# ProPrj_wildCat_2025-03-20.net
KiCad netlist of a schematic drawn in EasyEDA Pro
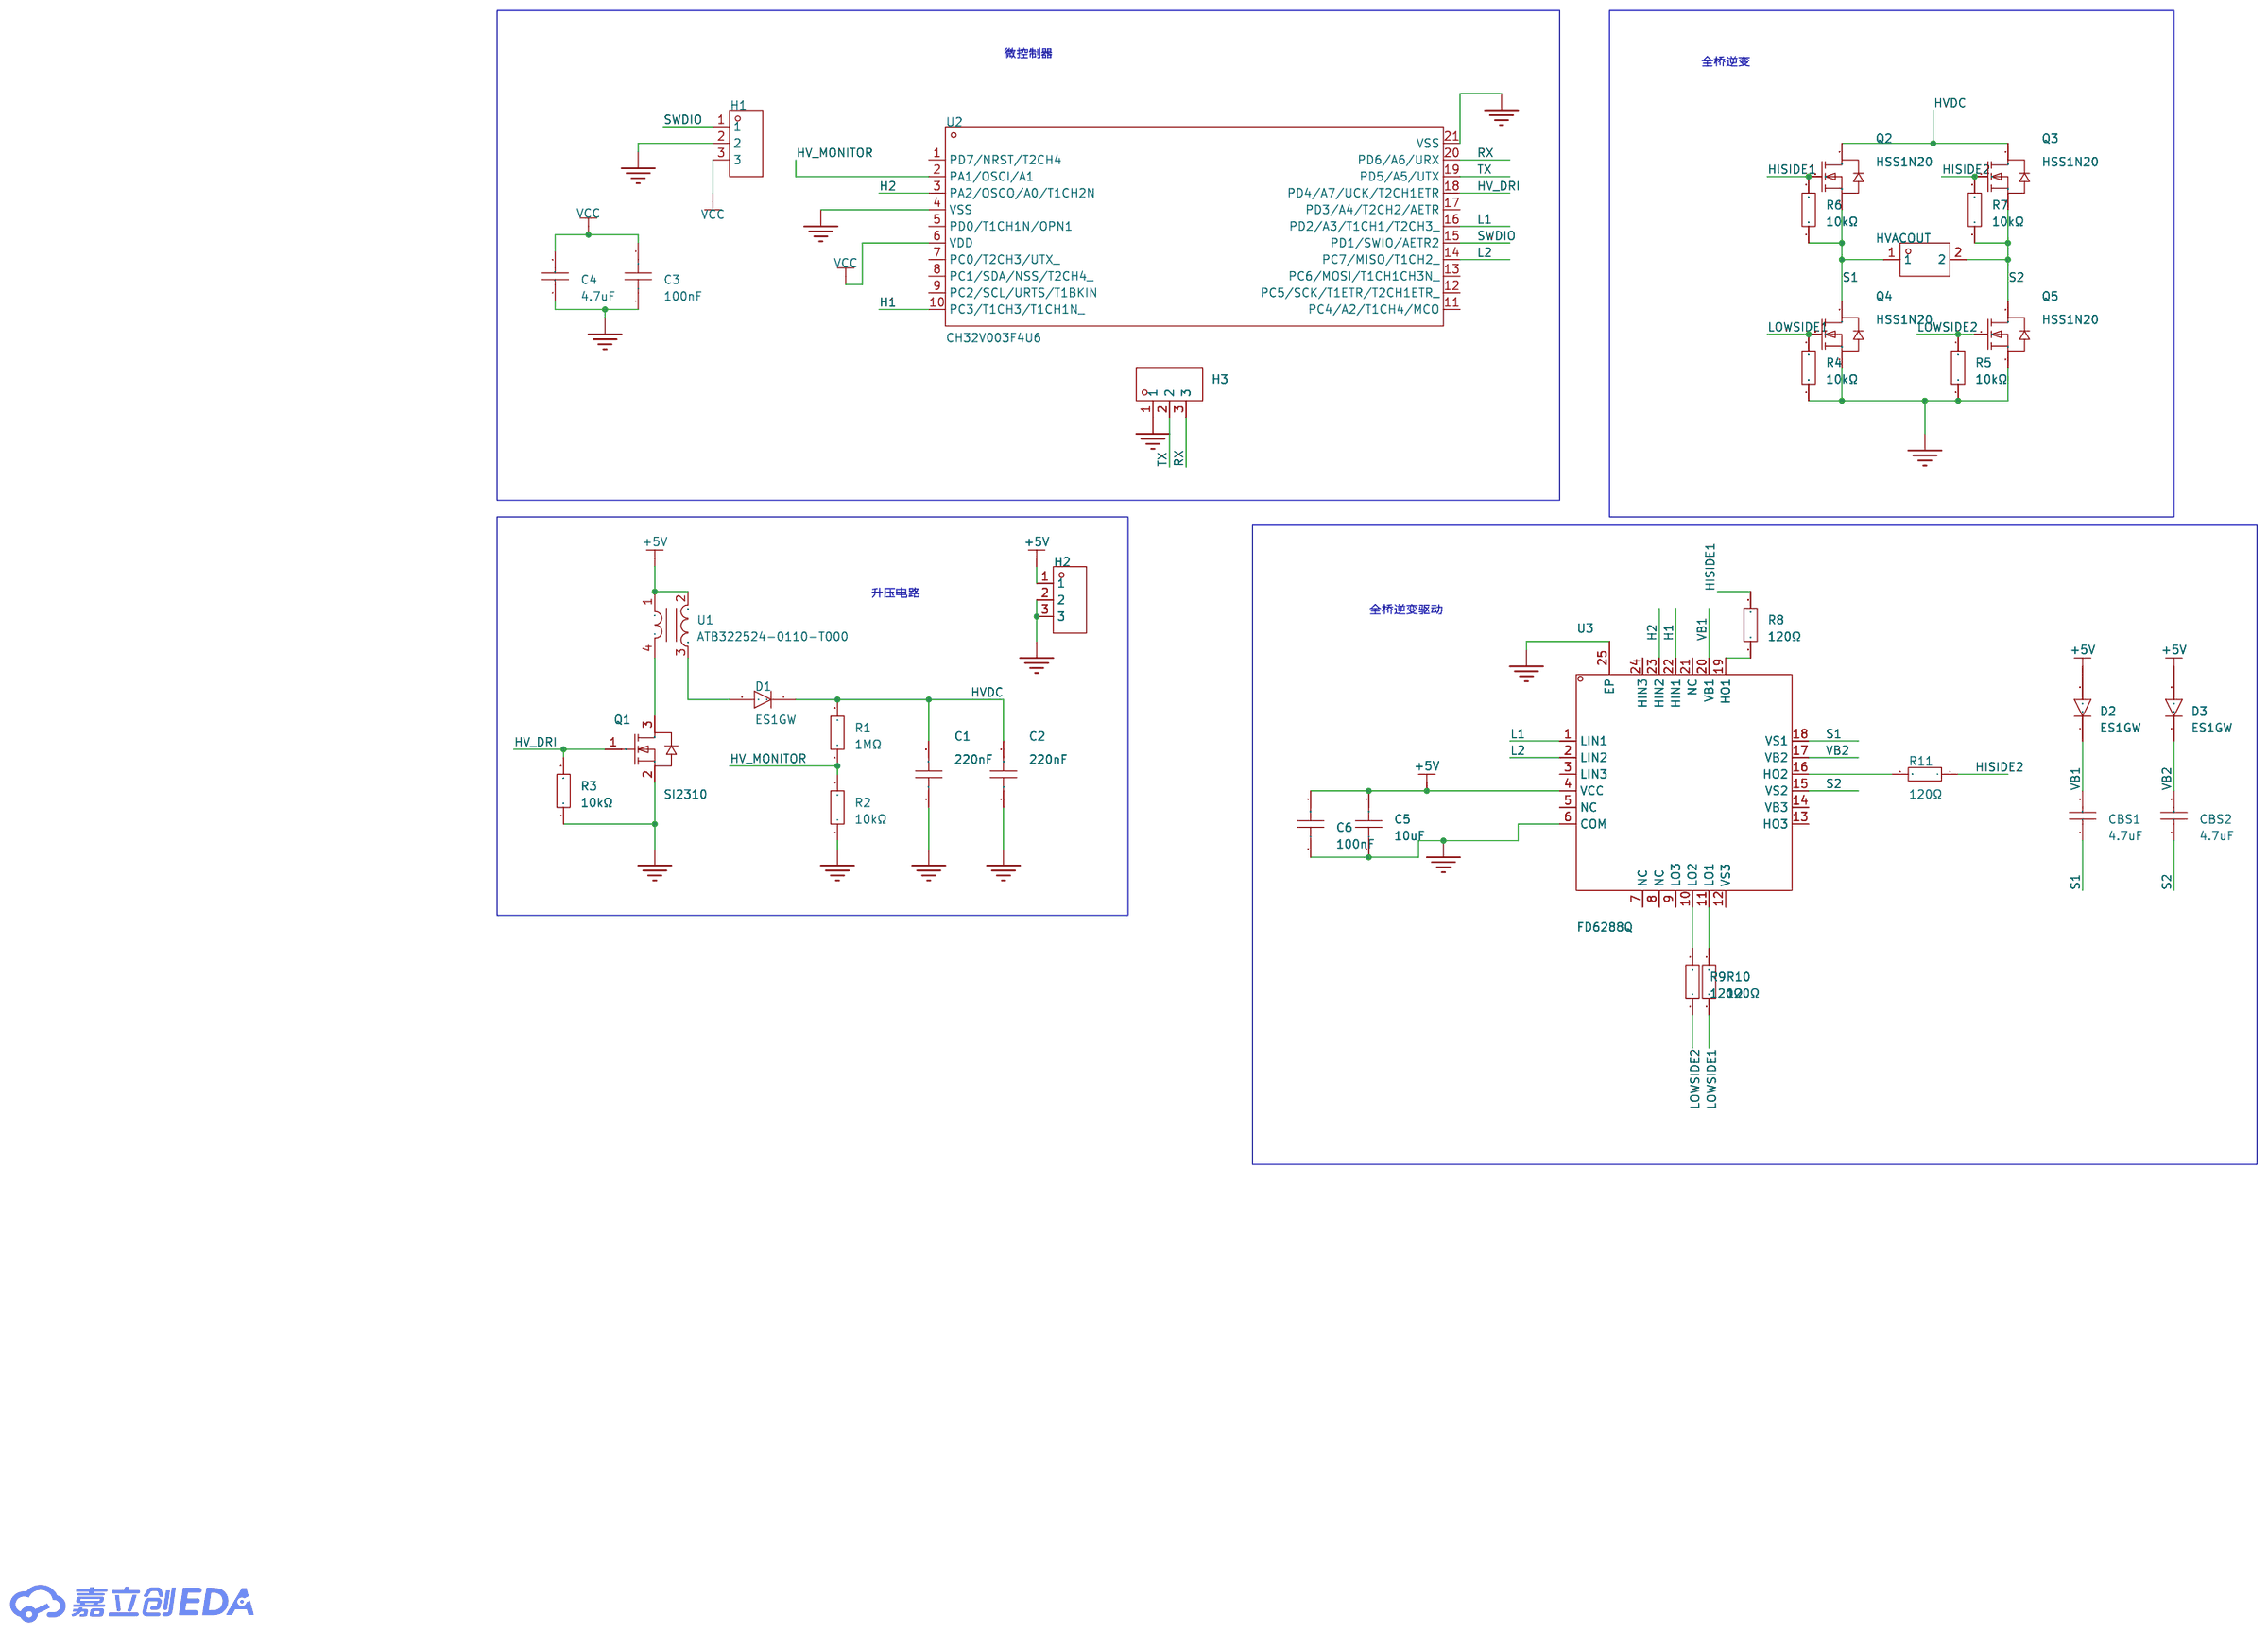
[diagram p0: schematic sheet]

(export (version "E")
  (design (tool "Eeschema 10.0.6"))
  (components
    (comp (ref "C1")
      (value "220nF")
      (footprint "easyedapro:C1210")
      (description "容值:220nF;精度:±10%;额定电压:250V;材质(温度系数):X7R;")
      (fields
        (field (name "Manufacturer Part") "CC1210KKX7RYBB224")
        (field (name "Manufacturer") "YAGEO(国巨)")
      )
      (libsource (lib "easyedapro") (part "CC1210KKX7RYBB224"))
    )
    (comp (ref "C2")
      (value "220nF")
      (footprint "easyedapro:C1210")
      (description "容值:220nF;精度:±10%;额定电压:250V;材质(温度系数):X7R;")
      (fields
        (field (name "Manufacturer Part") "CC1210KKX7RYBB224")
        (field (name "Manufacturer") "YAGEO(国巨)")
      )
      (libsource (lib "easyedapro") (part "CC1210KKX7RYBB224"))
    )
    (comp (ref "C3")
      (value "100nF")
      (footprint "easyedapro:C0603")
      (description "容值:100nF;精度:±10%;额定电压:50V;温度系数:X7R;")
      (fields
        (field (name "Manufacturer Part") "CGA0603X7R104K500JT")
        (field (name "Manufacturer") "HRE(芯声)")
      )
      (libsource (lib "easyedapro") (part "CGA0603X7R104K500JT"))
    )
    (comp (ref "C4")
      (value "4.7uF")
      (footprint "easyedapro:C0805")
      (description "容值:4.7uF;精度:±10%;额定电压:50V;材质(温度系数):X5R;")
      (fields
        (field (name "Manufacturer Part") "CL21A475KBQNNNE")
        (field (name "Manufacturer") "SAMSUNG(三星)")
      )
      (libsource (lib "easyedapro") (part "CL21A475KBQNNNE"))
    )
    (comp (ref "C5")
      (value "10uF")
      (footprint "easyedapro:C1206")
      (description "容值:10uF;精度:±10%;额定电压:50V;温度系数:X5R;")
      (fields
        (field (name "Manufacturer Part") "HGC1206R5106K500NSPJ")
        (field (name "Manufacturer") "Chinocera(华瓷)")
      )
      (libsource (lib "easyedapro") (part "HGC1206R5106K500NSPJ"))
    )
    (comp (ref "C6")
      (value "100nF")
      (footprint "easyedapro:C0603")
      (description "容值:100nF;精度:±10%;额定电压:50V;温度系数:X7R;")
      (fields
        (field (name "Manufacturer Part") "CGA0603X7R104K500JT")
        (field (name "Manufacturer") "HRE(芯声)")
      )
      (libsource (lib "easyedapro") (part "CGA0603X7R104K500JT"))
    )
    (comp (ref "CBS1")
      (value "4.7uF")
      (footprint "easyedapro:C0805")
      (description "容值:4.7uF;精度:±10%;额定电压:50V;材质(温度系数):X5R;")
      (fields
        (field (name "Manufacturer Part") "CL21A475KBQNNNE")
        (field (name "Manufacturer") "SAMSUNG(三星)")
      )
      (libsource (lib "easyedapro") (part "CL21A475KBQNNNE"))
    )
    (comp (ref "CBS2")
      (value "4.7uF")
      (footprint "easyedapro:C0805")
      (description "容值:4.7uF;精度:±10%;额定电压:50V;材质(温度系数):X5R;")
      (fields
        (field (name "Manufacturer Part") "CL21A475KBQNNNE")
        (field (name "Manufacturer") "SAMSUNG(三星)")
      )
      (libsource (lib "easyedapro") (part "CL21A475KBQNNNE"))
    )
    (comp (ref "D1")
      (value "ES1GW")
      (footprint "easyedapro:SOD-123FL_L2.7-W1.8-LS3.8-RD")
      (description "二极管配置:独立式;正向压降(Vf):1.25V@1A;直流反向耐压(Vr):400V;整流电流:1A;反向恢复时间(trr):35ns;")
      (fields (field (name "Manufacturer") "晶导微电子"))
      (libsource (lib "easyedapro") (part "ES1GW"))
    )
    (comp (ref "D2")
      (value "ES1GW")
      (footprint "easyedapro:SOD-123FL_L2.7-W1.8-LS3.8-RD")
      (description "二极管配置:独立式;正向压降(Vf):1.25V@1A;直流反向耐压(Vr):400V;整流电流:1A;反向恢复时间(trr):35ns;")
      (fields (field (name "Manufacturer") "晶导微电子"))
      (libsource (lib "easyedapro") (part "ES1GW"))
    )
    (comp (ref "D3")
      (value "ES1GW")
      (footprint "easyedapro:SOD-123FL_L2.7-W1.8-LS3.8-RD")
      (description "二极管配置:独立式;正向压降(Vf):1.25V@1A;直流反向耐压(Vr):400V;整流电流:1A;反向恢复时间(trr):35ns;")
      (fields (field (name "Manufacturer") "晶导微电子"))
      (libsource (lib "easyedapro") (part "ES1GW"))
    )
    (comp (ref "H1")
      (value "~")
      (footprint "easyedapro:HDR-TH_3P-P2.54-V-F")
      (libsource (lib "easyedapro") (part "PM254V-11-03-H85"))
    )
    (comp (ref "H2")
      (value "~")
      (footprint "easyedapro:HDR-TH_3P-P2.54-V-F")
      (libsource (lib "easyedapro") (part "PM254V-11-03-H85"))
    )
    (comp (ref "H3")
      (value "~")
      (footprint "easyedapro:HDR-TH_3P-P2.54-V-F")
      (libsource (lib "easyedapro") (part "PM254V-11-03-H85"))
    )
    (comp (ref "HVACOUT")
      (value "~")
      (footprint "easyedapro:HDR-TH_2P-P2.54-V-M-2")
      (libsource (lib "easyedapro") (part "HDR-M-2.54_2x1"))
    )
    (comp (ref "Q1")
      (value "SI2310")
      (footprint "easyedapro:SOT-23_L2.9-W1.3-P1.90-LS2.4-BR")
      (description "类型:-;漏源电压(Vdss):60V;连续漏极电流(Id):3A;导通电阻(RDS(on)):125mΩ@4.5V,3A;耗散功率(Pd):1.5W;阈值电压(Vgs(th)):500mV;")
      (fields (field (name "Manufacturer") "GOODWORK(固得沃克)"))
      (libsource (lib "easyedapro") (part "SI2310_C2938374"))
    )
    (comp (ref "Q2")
      (value "HSS1N20")
      (footprint "easyedapro:SOT-23-3_L2.9-W1.6-P1.90-LS2.8-BR")
      (fields (field (name "Manufacturer") "HUASHUO(华朔)"))
      (libsource (lib "easyedapro") (part "HSS1N20"))
    )
    (comp (ref "Q3")
      (value "HSS1N20")
      (footprint "easyedapro:SOT-23-3_L2.9-W1.6-P1.90-LS2.8-BR")
      (fields (field (name "Manufacturer") "HUASHUO(华朔)"))
      (libsource (lib "easyedapro") (part "HSS1N20"))
    )
    (comp (ref "Q4")
      (value "HSS1N20")
      (footprint "easyedapro:SOT-23-3_L2.9-W1.6-P1.90-LS2.8-BR")
      (fields (field (name "Manufacturer") "HUASHUO(华朔)"))
      (libsource (lib "easyedapro") (part "HSS1N20"))
    )
    (comp (ref "Q5")
      (value "HSS1N20")
      (footprint "easyedapro:SOT-23-3_L2.9-W1.6-P1.90-LS2.8-BR")
      (fields (field (name "Manufacturer") "HUASHUO(华朔)"))
      (libsource (lib "easyedapro") (part "HSS1N20"))
    )
    (comp (ref "R1")
      (value "1MΩ")
      (footprint "easyedapro:R0603")
      (description "电阻类型:厚膜电阻;阻值:1MΩ;精度:±1%;功率:100mW;最大工作电压:75V;温度系数:±100ppm/°C;")
      (fields
        (field (name "Manufacturer Part") "0603WAF1004T5E")
        (field (name "Manufacturer") "UNI-ROYAL(厚声)")
      )
      (libsource (lib "easyedapro") (part "0603WAF1004T5E"))
    )
    (comp (ref "R2")
      (value "10kΩ")
      (footprint "easyedapro:R0402")
      (description "电阻类型:厚膜电阻;阻值:10kΩ;精度:±1%;功率:62.5mW;最大工作电压:50V;温度系数:±100ppm/°C;")
      (fields
        (field (name "Manufacturer Part") "0603WAF1002T5E")
        (field (name "Manufacturer") "UNI-ROYAL(厚声)")
      )
      (libsource (lib "easyedapro") (part "0402WGF1002TCE"))
    )
    (comp (ref "R3")
      (value "10kΩ")
      (footprint "easyedapro:R0402")
      (description "电阻类型:厚膜电阻;阻值:10kΩ;精度:±1%;功率:62.5mW;最大工作电压:50V;温度系数:±100ppm/°C;")
      (fields
        (field (name "Manufacturer Part") "0603WAF1002T5E")
        (field (name "Manufacturer") "UNI-ROYAL(厚声)")
      )
      (libsource (lib "easyedapro") (part "0402WGF1002TCE"))
    )
    (comp (ref "R4")
      (value "10kΩ")
      (footprint "easyedapro:R0402")
      (description "电阻类型:厚膜电阻;阻值:10kΩ;精度:±1%;功率:62.5mW;最大工作电压:50V;温度系数:±100ppm/°C;")
      (fields
        (field (name "Manufacturer Part") "0603WAF1002T5E")
        (field (name "Manufacturer") "UNI-ROYAL(厚声)")
      )
      (libsource (lib "easyedapro") (part "0402WGF1002TCE"))
    )
    (comp (ref "R5")
      (value "10kΩ")
      (footprint "easyedapro:R0402")
      (description "电阻类型:厚膜电阻;阻值:10kΩ;精度:±1%;功率:62.5mW;最大工作电压:50V;温度系数:±100ppm/°C;")
      (fields
        (field (name "Manufacturer Part") "0603WAF1002T5E")
        (field (name "Manufacturer") "UNI-ROYAL(厚声)")
      )
      (libsource (lib "easyedapro") (part "0402WGF1002TCE"))
    )
    (comp (ref "R6")
      (value "10kΩ")
      (footprint "easyedapro:R0402")
      (description "电阻类型:厚膜电阻;阻值:10kΩ;精度:±1%;功率:62.5mW;最大工作电压:50V;温度系数:±100ppm/°C;")
      (fields
        (field (name "Manufacturer Part") "0603WAF1002T5E")
        (field (name "Manufacturer") "UNI-ROYAL(厚声)")
      )
      (libsource (lib "easyedapro") (part "0402WGF1002TCE"))
    )
    (comp (ref "R7")
      (value "10kΩ")
      (footprint "easyedapro:R0402")
      (description "电阻类型:厚膜电阻;阻值:10kΩ;精度:±1%;功率:62.5mW;最大工作电压:50V;温度系数:±100ppm/°C;")
      (fields
        (field (name "Manufacturer Part") "0603WAF1002T5E")
        (field (name "Manufacturer") "UNI-ROYAL(厚声)")
      )
      (libsource (lib "easyedapro") (part "0402WGF1002TCE"))
    )
    (comp (ref "R8")
      (value "120Ω")
      (footprint "easyedapro:R0603")
      (description "电阻类型:厚膜电阻;阻值:120Ω;精度:±1%;功率:100mW;最大工作电压:75V;温度系数:±100ppm/°C;")
      (fields
        (field (name "Manufacturer Part") "0603WAF1200T5E")
        (field (name "Manufacturer") "UNI-ROYAL(厚声)")
      )
      (libsource (lib "easyedapro") (part "0603WAF1200T5E"))
    )
    (comp (ref "R9")
      (value "120Ω")
      (footprint "easyedapro:R0603")
      (description "电阻类型:厚膜电阻;阻值:120Ω;精度:±1%;功率:100mW;最大工作电压:75V;温度系数:±100ppm/°C;")
      (fields
        (field (name "Manufacturer Part") "0603WAF1200T5E")
        (field (name "Manufacturer") "UNI-ROYAL(厚声)")
      )
      (libsource (lib "easyedapro") (part "0603WAF1200T5E"))
    )
    (comp (ref "R10")
      (value "120Ω")
      (footprint "easyedapro:R0603")
      (description "电阻类型:厚膜电阻;阻值:120Ω;精度:±1%;功率:100mW;最大工作电压:75V;温度系数:±100ppm/°C;")
      (fields
        (field (name "Manufacturer Part") "0603WAF1200T5E")
        (field (name "Manufacturer") "UNI-ROYAL(厚声)")
      )
      (libsource (lib "easyedapro") (part "0603WAF1200T5E"))
    )
    (comp (ref "R11")
      (value "120Ω")
      (footprint "easyedapro:R0603")
      (description "电阻类型:厚膜电阻;阻值:120Ω;精度:±1%;功率:100mW;最大工作电压:75V;温度系数:±100ppm/°C;")
      (fields
        (field (name "Manufacturer Part") "0603WAF1200T5E")
        (field (name "Manufacturer") "UNI-ROYAL(厚声)")
      )
      (libsource (lib "easyedapro") (part "0603WAF1200T5E"))
    )
    (comp (ref "U1")
      (value "ATB322524-0110-T000")
      (footprint "easyedapro:XFMR-SMD_ATB322515-0110-T000")
      (description "初级电压:-;次级电压:-;输出电流:-;功率:-;")
      (fields (field (name "Manufacturer") "TDK"))
      (libsource (lib "easyedapro") (part "ATB322524-0110-T000"))
    )
    (comp (ref "U2")
      (value "CH32V003F4U6")
      (footprint "easyedapro:QFN-20_L3.0-W3.0-P0.40-TL-EP1.7")
      (description "CPU内核:RISC-V;程序存储容量:16KB;RAM总容量:2KB;GPIO端口数量:18;工作电压范围:-;CPU最大主频:48MHz;程序存储器类型:-;应用领域:-;")
      (fields (field (name "Manufacturer") "WCH(南京沁恒)"))
      (libsource (lib "easyedapro") (part "CH32V003F4U6"))
    )
    (comp (ref "U3")
      (value "FD6288Q")
      (footprint "easyedapro:QFN-24_L4.0-W4.0-P0.50-BL-EP2.6")
      (fields (field (name "Manufacturer") "Fortior Tech(峰岹)"))
      (libsource (lib "easyedapro") (part "FD6288Q_C328453"))
    )
  )
  (nets
    (net (code "1") (name "+5V") (class "Default")
      (node (ref "C5") (pin "2") (pinfunction "2_2") (pintype "unspecified"))
      (node (ref "C6") (pin "2") (pinfunction "2_2") (pintype "unspecified"))
      (node (ref "D2") (pin "2") (pinfunction "A_2") (pintype "unspecified"))
      (node (ref "D3") (pin "2") (pinfunction "A_2") (pintype "unspecified"))
      (node (ref "H2") (pin "1") (pinfunction "1_1") (pintype "unspecified"))
      (node (ref "U1") (pin "1") (pinfunction "1_1") (pintype "unspecified"))
      (node (ref "U1") (pin "2") (pinfunction "2_2") (pintype "unspecified"))
      (node (ref "U3") (pin "4") (pinfunction "VCC_4") (pintype "unspecified"))
    )
    (net (code "2") (name "/H1") (class "Default")
      (node (ref "U2") (pin "10") (pinfunction "PC3/T1CH3/T1CH1N__10") (pintype "unspecified"))
      (node (ref "U3") (pin "22") (pinfunction "HIN1_22") (pintype "unspecified"))
    )
    (net (code "3") (name "/H2") (class "Default")
      (node (ref "U2") (pin "3") (pinfunction "PA2/OSCO/A0/T1CH2N_3") (pintype "unspecified"))
      (node (ref "U3") (pin "23") (pinfunction "HIN2_23") (pintype "unspecified"))
    )
    (net (code "4") (name "/HISIDE1") (class "Default")
      (node (ref "Q2") (pin "1") (pinfunction "G_1") (pintype "unspecified"))
      (node (ref "R6") (pin "2") (pinfunction "2_2") (pintype "input"))
      (node (ref "R8") (pin "2") (pinfunction "2_2") (pintype "input"))
    )
    (net (code "5") (name "/HISIDE2") (class "Default")
      (node (ref "Q3") (pin "1") (pinfunction "G_1") (pintype "unspecified"))
      (node (ref "R11") (pin "1") (pinfunction "1_1") (pintype "input"))
      (node (ref "R7") (pin "2") (pinfunction "2_2") (pintype "input"))
    )
    (net (code "6") (name "/HVDC") (class "Default")
      (node (ref "C1") (pin "2") (pinfunction "2_2") (pintype "unspecified"))
      (node (ref "C2") (pin "2") (pinfunction "2_2") (pintype "unspecified"))
      (node (ref "D1") (pin "1") (pinfunction "C_1") (pintype "unspecified"))
      (node (ref "Q2") (pin "3") (pinfunction "D_3") (pintype "unspecified"))
      (node (ref "Q3") (pin "3") (pinfunction "D_3") (pintype "unspecified"))
      (node (ref "R1") (pin "2") (pinfunction "2_2") (pintype "input"))
    )
    (net (code "7") (name "/HV_DRI") (class "Default")
      (node (ref "Q1") (pin "1") (pinfunction "G_1") (pintype "unspecified"))
      (node (ref "R3") (pin "2") (pinfunction "2_2") (pintype "input"))
      (node (ref "U2") (pin "18") (pinfunction "PD4/A7/UCK/T2CH1ETR_18") (pintype "unspecified"))
    )
    (net (code "8") (name "/HV_MONITOR") (class "Default")
      (node (ref "R1") (pin "1") (pinfunction "1_1") (pintype "input"))
      (node (ref "R2") (pin "2") (pinfunction "2_2") (pintype "input"))
      (node (ref "U2") (pin "2") (pinfunction "PA1/OSCI/A1_2") (pintype "unspecified"))
    )
    (net (code "9") (name "/L1") (class "Default")
      (node (ref "U2") (pin "16") (pinfunction "PD2/A3/T1CH1/T2CH3__16") (pintype "unspecified"))
      (node (ref "U3") (pin "1") (pinfunction "LIN1_1") (pintype "unspecified"))
    )
    (net (code "10") (name "/L2") (class "Default")
      (node (ref "U2") (pin "14") (pinfunction "PC7/MISO/T1CH2__14") (pintype "unspecified"))
      (node (ref "U3") (pin "2") (pinfunction "LIN2_2") (pintype "unspecified"))
    )
    (net (code "11") (name "/LOWSIDE1") (class "Default")
      (node (ref "Q4") (pin "1") (pinfunction "G_1") (pintype "unspecified"))
      (node (ref "R10") (pin "1") (pinfunction "1_1") (pintype "input"))
      (node (ref "R4") (pin "2") (pinfunction "2_2") (pintype "input"))
    )
    (net (code "12") (name "/LOWSIDE2") (class "Default")
      (node (ref "Q5") (pin "1") (pinfunction "G_1") (pintype "unspecified"))
      (node (ref "R5") (pin "2") (pinfunction "2_2") (pintype "input"))
      (node (ref "R9") (pin "1") (pinfunction "1_1") (pintype "input"))
    )
    (net (code "13") (name "/RX") (class "Default")
      (node (ref "H3") (pin "3") (pinfunction "3_3") (pintype "unspecified"))
      (node (ref "U2") (pin "20") (pinfunction "PD6/A6/URX_20") (pintype "unspecified"))
    )
    (net (code "14") (name "/S1") (class "Default")
      (node (ref "CBS1") (pin "1") (pinfunction "1_1") (pintype "input"))
      (node (ref "HVACOUT") (pin "1") (pinfunction "1_1") (pintype "input"))
      (node (ref "Q2") (pin "2") (pinfunction "S_2") (pintype "unspecified"))
      (node (ref "Q4") (pin "3") (pinfunction "D_3") (pintype "unspecified"))
      (node (ref "R6") (pin "1") (pinfunction "1_1") (pintype "input"))
      (node (ref "U3") (pin "18") (pinfunction "VS1_18") (pintype "unspecified"))
    )
    (net (code "15") (name "/S2") (class "Default")
      (node (ref "CBS2") (pin "1") (pinfunction "1_1") (pintype "input"))
      (node (ref "HVACOUT") (pin "2") (pinfunction "2_2") (pintype "input"))
      (node (ref "Q3") (pin "2") (pinfunction "S_2") (pintype "unspecified"))
      (node (ref "Q5") (pin "3") (pinfunction "D_3") (pintype "unspecified"))
      (node (ref "R7") (pin "1") (pinfunction "1_1") (pintype "input"))
      (node (ref "U3") (pin "15") (pinfunction "VS2_15") (pintype "unspecified"))
    )
    (net (code "16") (name "/SWDIO") (class "Default")
      (node (ref "H1") (pin "1") (pinfunction "1_1") (pintype "unspecified"))
      (node (ref "U2") (pin "15") (pinfunction "PD1/SWIO/AETR2_15") (pintype "unspecified"))
    )
    (net (code "17") (name "/TX") (class "Default")
      (node (ref "H3") (pin "2") (pinfunction "2_2") (pintype "unspecified"))
      (node (ref "U2") (pin "19") (pinfunction "PD5/A5/UTX_19") (pintype "unspecified"))
    )
    (net (code "18") (name "/VB1") (class "Default")
      (node (ref "CBS1") (pin "2") (pinfunction "2_2") (pintype "input"))
      (node (ref "D2") (pin "1") (pinfunction "C_1") (pintype "unspecified"))
      (node (ref "U3") (pin "20") (pinfunction "VB1_20") (pintype "unspecified"))
    )
    (net (code "19") (name "/VB2") (class "Default")
      (node (ref "CBS2") (pin "2") (pinfunction "2_2") (pintype "input"))
      (node (ref "D3") (pin "1") (pinfunction "C_1") (pintype "unspecified"))
      (node (ref "U3") (pin "17") (pinfunction "VB2_17") (pintype "unspecified"))
    )
    (net (code "20") (name "GND") (class "Default")
      (node (ref "C1") (pin "1") (pinfunction "1_1") (pintype "unspecified"))
      (node (ref "C2") (pin "1") (pinfunction "1_1") (pintype "unspecified"))
      (node (ref "C3") (pin "1") (pinfunction "1_1") (pintype "unspecified"))
      (node (ref "C4") (pin "1") (pinfunction "1_1") (pintype "input"))
      (node (ref "C5") (pin "1") (pinfunction "1_1") (pintype "unspecified"))
      (node (ref "C6") (pin "1") (pinfunction "1_1") (pintype "unspecified"))
      (node (ref "H1") (pin "2") (pinfunction "2_2") (pintype "unspecified"))
      (node (ref "H2") (pin "2") (pinfunction "2_2") (pintype "unspecified"))
      (node (ref "H2") (pin "3") (pinfunction "3_3") (pintype "unspecified"))
      (node (ref "H3") (pin "1") (pinfunction "1_1") (pintype "unspecified"))
      (node (ref "Q1") (pin "2") (pinfunction "S_2") (pintype "unspecified"))
      (node (ref "Q4") (pin "2") (pinfunction "S_2") (pintype "unspecified"))
      (node (ref "Q5") (pin "2") (pinfunction "S_2") (pintype "unspecified"))
      (node (ref "R2") (pin "1") (pinfunction "1_1") (pintype "input"))
      (node (ref "R3") (pin "1") (pinfunction "1_1") (pintype "input"))
      (node (ref "R4") (pin "1") (pinfunction "1_1") (pintype "input"))
      (node (ref "R5") (pin "1") (pinfunction "1_1") (pintype "input"))
      (node (ref "U2") (pin "21") (pinfunction "VSS_21") (pintype "unspecified"))
      (node (ref "U2") (pin "4") (pinfunction "VSS_4") (pintype "unspecified"))
      (node (ref "U3") (pin "25") (pinfunction "EP_25") (pintype "unspecified"))
      (node (ref "U3") (pin "6") (pinfunction "COM_6") (pintype "unspecified"))
    )
    (net (code "21") (name "Net-(D1-A)") (class "Default")
      (node (ref "D1") (pin "2") (pinfunction "A_2") (pintype "unspecified"))
      (node (ref "U1") (pin "3") (pinfunction "3_3") (pintype "unspecified"))
    )
    (net (code "22") (name "Net-(Q1-D)") (class "Default")
      (node (ref "Q1") (pin "3") (pinfunction "D_3") (pintype "unspecified"))
      (node (ref "U1") (pin "4") (pinfunction "4_4") (pintype "unspecified"))
    )
    (net (code "23") (name "Net-(U3-HO1)") (class "Default")
      (node (ref "R8") (pin "1") (pinfunction "1_1") (pintype "input"))
      (node (ref "U3") (pin "19") (pinfunction "HO1_19") (pintype "unspecified"))
    )
    (net (code "24") (name "Net-(U3-HO2)") (class "Default")
      (node (ref "R11") (pin "2") (pinfunction "2_2") (pintype "input"))
      (node (ref "U3") (pin "16") (pinfunction "HO2_16") (pintype "unspecified"))
    )
    (net (code "25") (name "Net-(U3-LO1)") (class "Default")
      (node (ref "R10") (pin "2") (pinfunction "2_2") (pintype "input"))
      (node (ref "U3") (pin "11") (pinfunction "LO1_11") (pintype "unspecified"))
    )
    (net (code "26") (name "Net-(U3-LO2)") (class "Default")
      (node (ref "R9") (pin "2") (pinfunction "2_2") (pintype "input"))
      (node (ref "U3") (pin "10") (pinfunction "LO2_10") (pintype "unspecified"))
    )
    (net (code "27") (name "VCC") (class "Default")
      (node (ref "C3") (pin "2") (pinfunction "2_2") (pintype "unspecified"))
      (node (ref "C4") (pin "2") (pinfunction "2_2") (pintype "input"))
      (node (ref "H1") (pin "3") (pinfunction "3_3") (pintype "unspecified"))
      (node (ref "U2") (pin "6") (pinfunction "VDD_6") (pintype "unspecified"))
    )
    (net (code "28") (name "unconnected-(U2-PC0{slash}T2CH3{slash}UTX_-Pad7)") (class "Default")
      (node (ref "U2") (pin "7") (pinfunction "PC0/T2CH3/UTX__7") (pintype "unspecified"))
    )
    (net (code "29") (name "unconnected-(U2-PC1{slash}SDA{slash}NSS{slash}T2CH4_-Pad8)") (class "Default")
      (node (ref "U2") (pin "8") (pinfunction "PC1/SDA/NSS/T2CH4__8") (pintype "unspecified"))
    )
    (net (code "30") (name "unconnected-(U2-PC2{slash}SCL{slash}URTS{slash}T1BKIN-Pad9)") (class "Default")
      (node (ref "U2") (pin "9") (pinfunction "PC2/SCL/URTS/T1BKIN_9") (pintype "unspecified"))
    )
    (net (code "31") (name "unconnected-(U2-PC4{slash}A2{slash}T1CH4{slash}MCO-Pad11)") (class "Default")
      (node (ref "U2") (pin "11") (pinfunction "PC4/A2/T1CH4/MCO_11") (pintype "unspecified"))
    )
    (net (code "32") (name "unconnected-(U2-PC5{slash}SCK{slash}T1ETR{slash}T2CH1ETR_-Pad12)") (class "Default")
      (node (ref "U2") (pin "12") (pinfunction "PC5/SCK/T1ETR/T2CH1ETR__12") (pintype "unspecified"))
    )
    (net (code "33") (name "unconnected-(U2-PC6{slash}MOSI{slash}T1CH1CH3N_-Pad13)") (class "Default")
      (node (ref "U2") (pin "13") (pinfunction "PC6/MOSI/T1CH1CH3N__13") (pintype "unspecified"))
    )
    (net (code "34") (name "unconnected-(U2-PD0{slash}T1CH1N{slash}OPN1-Pad5)") (class "Default")
      (node (ref "U2") (pin "5") (pinfunction "PD0/T1CH1N/OPN1_5") (pintype "unspecified"))
    )
    (net (code "35") (name "unconnected-(U2-PD3{slash}A4{slash}T2CH2{slash}AETR-Pad17)") (class "Default")
      (node (ref "U2") (pin "17") (pinfunction "PD3/A4/T2CH2/AETR_17") (pintype "unspecified"))
    )
    (net (code "36") (name "unconnected-(U2-PD7{slash}NRST{slash}T2CH4-Pad1)") (class "Default")
      (node (ref "U2") (pin "1") (pinfunction "PD7/NRST/T2CH4_1") (pintype "unspecified"))
    )
    (net (code "37") (name "unconnected-(U3-HIN3-Pad24)") (class "Default")
      (node (ref "U3") (pin "24") (pinfunction "HIN3_24") (pintype "unspecified"))
    )
    (net (code "38") (name "unconnected-(U3-HO3-Pad13)") (class "Default")
      (node (ref "U3") (pin "13") (pinfunction "HO3_13") (pintype "unspecified"))
    )
    (net (code "39") (name "unconnected-(U3-LIN3-Pad3)") (class "Default")
      (node (ref "U3") (pin "3") (pinfunction "LIN3_3") (pintype "unspecified"))
    )
    (net (code "40") (name "unconnected-(U3-LO3-Pad9)") (class "Default")
      (node (ref "U3") (pin "9") (pinfunction "LO3_9") (pintype "unspecified"))
    )
    (net (code "41") (name "unconnected-(U3-NC-Pad5)") (class "Default")
      (node (ref "U3") (pin "5") (pinfunction "NC_5") (pintype "unspecified"))
    )
    (net (code "42") (name "unconnected-(U3-NC-Pad7)") (class "Default")
      (node (ref "U3") (pin "7") (pinfunction "NC_7") (pintype "unspecified"))
    )
    (net (code "43") (name "unconnected-(U3-NC-Pad8)") (class "Default")
      (node (ref "U3") (pin "8") (pinfunction "NC_8") (pintype "unspecified"))
    )
    (net (code "44") (name "unconnected-(U3-NC-Pad21)") (class "Default")
      (node (ref "U3") (pin "21") (pinfunction "NC_21") (pintype "unspecified"))
    )
    (net (code "45") (name "unconnected-(U3-VB3-Pad14)") (class "Default")
      (node (ref "U3") (pin "14") (pinfunction "VB3_14") (pintype "unspecified"))
    )
    (net (code "46") (name "unconnected-(U3-VS3-Pad12)") (class "Default")
      (node (ref "U3") (pin "12") (pinfunction "VS3_12") (pintype "unspecified"))
    )
  )
)
